# AltiumStm32Schematic.net
KiCad netlist of a schematic drawn in Altium Designer
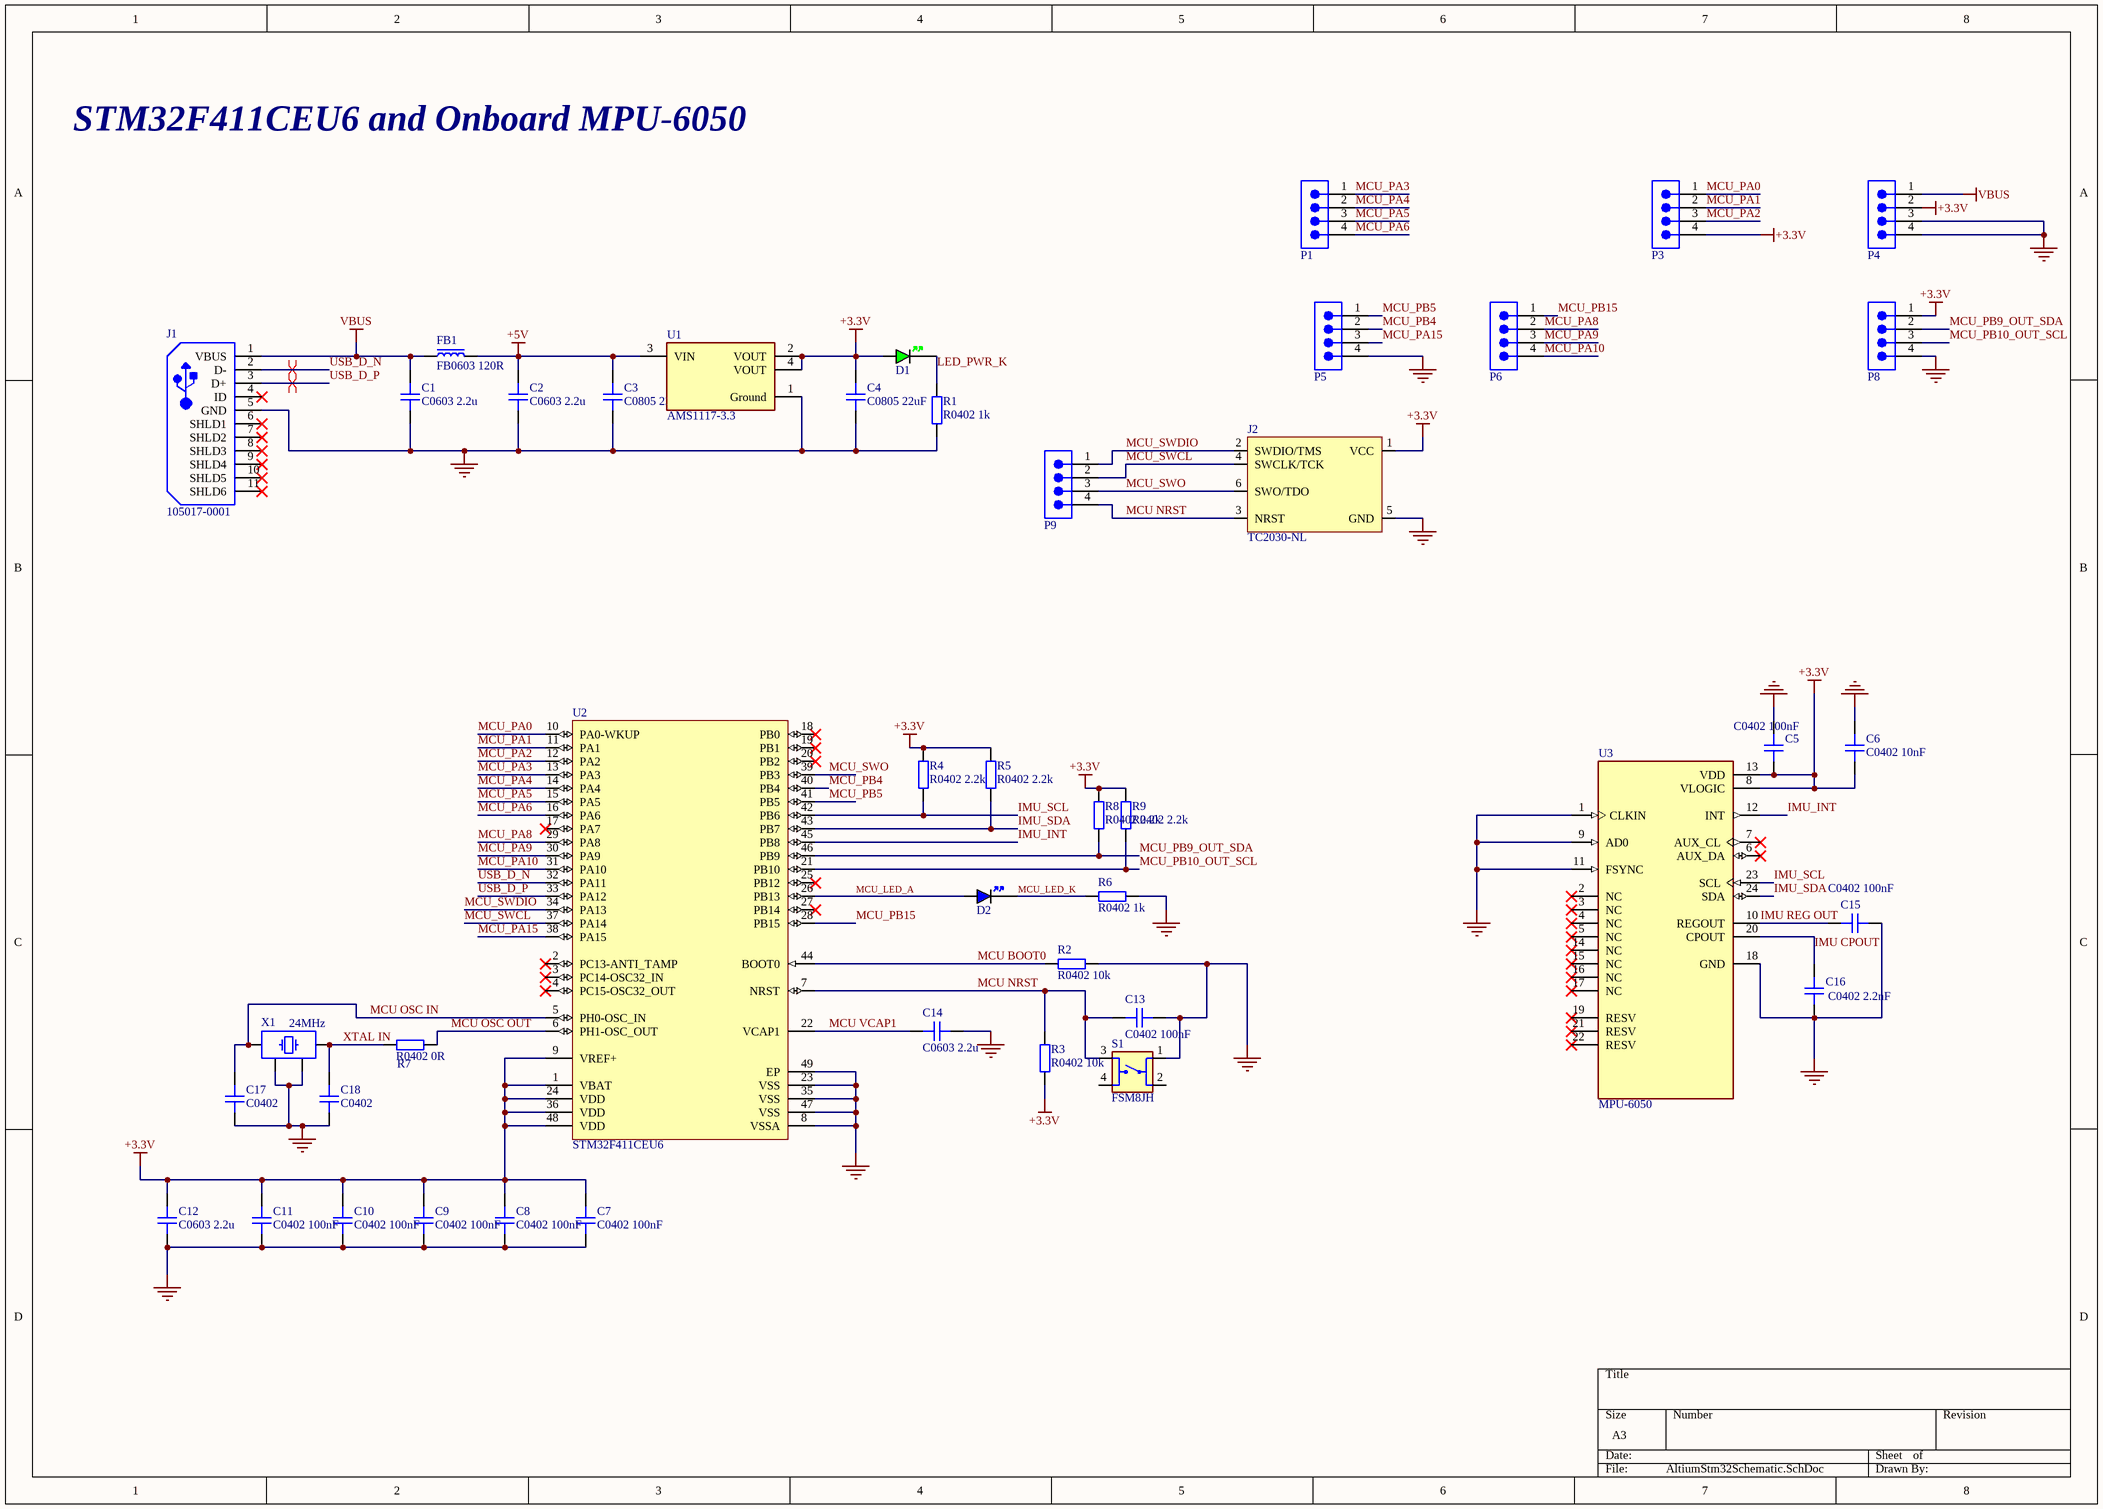
[diagram p0: AltiumStm32Schematic.SchDoc]

(export (version "E")
  (design (tool "Eeschema 10.0.6"))
  (components
    (comp (ref "C1")
      (value "C0603 2.2u")
      (footprint "CAP_0603")
      (description "Capacitor SMD 0603")
      (libsource (lib "Schematic-Lib-PhilsLab") (part "CAP_0603"))
    )
    (comp (ref "C2")
      (value "C0603 2.2u")
      (footprint "CAP_0603")
      (description "Capacitor SMD 0603")
      (libsource (lib "Schematic-Lib-PhilsLab") (part "CAP_0603"))
    )
    (comp (ref "C3")
      (value "C0805 22uF")
      (footprint "CAP_0805")
      (description "Capacitor SMD 0805 16V")
      (libsource (lib "Schematic-Lib-PhilsLab") (part "CAP_0805"))
    )
    (comp (ref "C4")
      (value "C0805 22uF")
      (footprint "CAP_0805")
      (description "Capacitor SMD 0805 16V")
      (libsource (lib "Schematic-Lib-PhilsLab") (part "CAP_0805"))
    )
    (comp (ref "C5")
      (value "C0402 100nF")
      (footprint "CAP_0402")
      (description "Capacitor SMD 0402")
      (libsource (lib "Schematic-Lib-PhilsLab") (part "CAP_0402"))
    )
    (comp (ref "C6")
      (value "C0402 10nF")
      (footprint "CAP_0402")
      (description "Capacitor SMD 0402")
      (libsource (lib "Schematic-Lib-PhilsLab") (part "CAP_0402"))
    )
    (comp (ref "C7")
      (value "C0402 100nF")
      (footprint "CAP_0402")
      (description "Capacitor SMD 0402")
      (libsource (lib "Schematic-Lib-PhilsLab") (part "CAP_0402"))
    )
    (comp (ref "C8")
      (value "C0402 100nF")
      (footprint "CAP_0402")
      (description "Capacitor SMD 0402")
      (libsource (lib "Schematic-Lib-PhilsLab") (part "CAP_0402"))
    )
    (comp (ref "C9")
      (value "C0402 100nF")
      (footprint "CAP_0402")
      (description "Capacitor SMD 0402")
      (libsource (lib "Schematic-Lib-PhilsLab") (part "CAP_0402"))
    )
    (comp (ref "C10")
      (value "C0402 100nF")
      (footprint "CAP_0402")
      (description "Capacitor SMD 0402")
      (libsource (lib "Schematic-Lib-PhilsLab") (part "CAP_0402"))
    )
    (comp (ref "C11")
      (value "C0402 100nF")
      (footprint "CAP_0402")
      (description "Capacitor SMD 0402")
      (libsource (lib "Schematic-Lib-PhilsLab") (part "CAP_0402"))
    )
    (comp (ref "C12")
      (value "C0603 2.2u")
      (footprint "CAP_0603")
      (description "Capacitor SMD 0603")
      (libsource (lib "Schematic-Lib-PhilsLab") (part "CAP_0603"))
    )
    (comp (ref "C13")
      (value "C0402 100nF")
      (footprint "CAP_0402")
      (description "Capacitor SMD 0402")
      (libsource (lib "Schematic-Lib-PhilsLab") (part "CAP_0402"))
    )
    (comp (ref "C14")
      (value "C0603 2.2u")
      (footprint "CAP_0603")
      (description "Capacitor SMD 0603")
      (libsource (lib "Schematic-Lib-PhilsLab") (part "CAP_0603"))
    )
    (comp (ref "C15")
      (value "C0402 100nF")
      (footprint "CAP_0402")
      (description "Capacitor SMD 0402")
      (libsource (lib "Schematic-Lib-PhilsLab") (part "CAP_0402"))
    )
    (comp (ref "C16")
      (value "C0402 2.2nF")
      (footprint "CAP_0402")
      (description "Capacitor SMD 0402")
      (libsource (lib "Schematic-Lib-PhilsLab") (part "CAP_0402"))
    )
    (comp (ref "C17")
      (value "C0402")
      (footprint "CAP_0402")
      (description "Capacitor SMD 0402 \r\nudemy'e göre 10pf")
      (libsource (lib "Schematic-Lib-PhilsLab") (part "CAP_0402"))
    )
    (comp (ref "C18")
      (value "C0402")
      (footprint "CAP_0402")
      (description "Capacitor SMD 0402 \r\nudemy'e göre 10pf")
      (libsource (lib "Schematic-Lib-PhilsLab") (part "CAP_0402"))
    )
    (comp (ref "D1")
      (value "GREEN")
      (footprint "LED_0402_GREEN")
      (description "LED 0402 GREEN SMD")
      (libsource (lib "Schematic-Lib-PhilsLab") (part "LED_0402_GREEN"))
    )
    (comp (ref "D2")
      (value "BLUE")
      (footprint "LED_0402_BLUE")
      (description "LED 0402 BLUE SMD")
      (libsource (lib "Schematic-Lib-PhilsLab") (part "LED_0402_BLUE"))
    )
    (comp (ref "FB1")
      (value "FB0603 120R")
      (footprint "FB_0603")
      (description "Ferrite Bead SMD 0603")
      (libsource (lib "Schematic-Lib-PhilsLab") (part "FB_0603"))
    )
    (comp (ref "J1")
      (value "105017-0001")
      (footprint "USB-MICRO-B_V")
      (fields (field (name "MANUFACTURER") "Molex"))
      (libsource (lib "Altium Content Vault") (part "USB-5-6SHLD"))
    )
    (comp (ref "J2")
      (value "TC2030-NL")
      (footprint "TC2030-NL-FP")
      (description "Tag-Connect No-Solder SWD Debug Connector (No Legs) DO NOT PLACE")
      (fields
        (field (name "MANUFACTURER") "Tag-Connect")
        (field (name "MANUFACTURER PART NUMBER") "TC2030-NL-FP")
      )
      (libsource (lib "Schematic-Lib-PhilsLab") (part "TC2030-NL"))
    )
    (comp (ref "P1")
      (value "61300411121")
      (footprint "61300411121")
      (description "WR-PHD Pin Header, THT, Vertical, pitch 2.54mm, 1 Row, 4P")
      (fields (field (name "MANUFACTURER") "Wurth Elektronik"))
      (libsource (lib "Altium_WR-PHD (rev24a)") (part "61300411121"))
    )
    (comp (ref "P3")
      (value "61300411121")
      (footprint "61300411121")
      (description "WR-PHD Pin Header, THT, Vertical, pitch 2.54mm, 1 Row, 4P")
      (fields (field (name "MANUFACTURER") "Wurth Elektronik"))
      (libsource (lib "Altium_WR-PHD (rev24a)") (part "61300411121"))
    )
    (comp (ref "P4")
      (value "61300411121")
      (footprint "61300411121")
      (description "WR-PHD Pin Header, THT, Vertical, pitch 2.54mm, 1 Row, 4P")
      (fields (field (name "MANUFACTURER") "Wurth Elektronik"))
      (libsource (lib "Altium_WR-PHD (rev24a)") (part "61300411121"))
    )
    (comp (ref "P5")
      (value "61300411121")
      (footprint "61300411121")
      (description "WR-PHD Pin Header, THT, Vertical, pitch 2.54mm, 1 Row, 4P")
      (fields (field (name "MANUFACTURER") "Wurth Elektronik"))
      (libsource (lib "Altium_WR-PHD (rev24a)") (part "61300411121"))
    )
    (comp (ref "P6")
      (value "61300411121")
      (footprint "61300411121")
      (description "WR-PHD Pin Header, THT, Vertical, pitch 2.54mm, 1 Row, 4P")
      (fields (field (name "MANUFACTURER") "Wurth Elektronik"))
      (libsource (lib "Altium_WR-PHD (rev24a)") (part "61300411121"))
    )
    (comp (ref "P8")
      (value "61300411121")
      (footprint "61300411121")
      (description "WR-PHD Pin Header, THT, Vertical, pitch 2.54mm, 1 Row, 4P")
      (fields (field (name "MANUFACTURER") "Wurth Elektronik"))
      (libsource (lib "Altium_WR-PHD (rev24a)") (part "61300411121"))
    )
    (comp (ref "P9")
      (value "61300411121")
      (footprint "61300411121")
      (description "WR-PHD Pin Header, THT, Vertical, pitch 2.54mm, 1 Row, 4P")
      (fields (field (name "MANUFACTURER") "Wurth Elektronik"))
      (libsource (lib "Altium_WR-PHD (rev24a)") (part "61300411121"))
    )
    (comp (ref "R1")
      (value "R0402 1k")
      (footprint "RES_0402")
      (description "Resistor SMD 0402")
      (libsource (lib "Schematic-Lib-PhilsLab") (part "RES_0402"))
    )
    (comp (ref "R2")
      (value "R0402 10k")
      (footprint "RES_0402")
      (description "Resistor SMD 0402")
      (libsource (lib "Schematic-Lib-PhilsLab") (part "RES_0402"))
    )
    (comp (ref "R3")
      (value "R0402 10k")
      (footprint "RES_0402")
      (description "Resistor SMD 0402")
      (libsource (lib "Schematic-Lib-PhilsLab") (part "RES_0402"))
    )
    (comp (ref "R4")
      (value "R0402 2.2k")
      (footprint "RES_0402")
      (description "Resistor SMD 0402")
      (libsource (lib "Schematic-Lib-PhilsLab") (part "RES_0402"))
    )
    (comp (ref "R5")
      (value "R0402 2.2k")
      (footprint "RES_0402")
      (description "Resistor SMD 0402")
      (libsource (lib "Schematic-Lib-PhilsLab") (part "RES_0402"))
    )
    (comp (ref "R6")
      (value "R0402 1k")
      (footprint "RES_0402")
      (description "Resistor SMD 0402")
      (libsource (lib "Schematic-Lib-PhilsLab") (part "RES_0402"))
    )
    (comp (ref "R7")
      (value "R0402 0R")
      (footprint "RES_0402")
      (description "Resistor SMD 0402")
      (libsource (lib "Schematic-Lib-PhilsLab") (part "RES_0402"))
    )
    (comp (ref "R8")
      (value "R0402 2.2k")
      (footprint "RES_0402")
      (description "Resistor SMD 0402")
      (libsource (lib "Schematic-Lib-PhilsLab") (part "RES_0402"))
    )
    (comp (ref "R9")
      (value "R0402 2.2k")
      (footprint "RES_0402")
      (description "Resistor SMD 0402")
      (libsource (lib "Schematic-Lib-PhilsLab") (part "RES_0402"))
    )
    (comp (ref "S1")
      (value "FSM8JH")
      (footprint "SW_FSM8JH")
      (description "Tactile Switch SPST-NO Top Actuated Through Hole")
      (fields (field (name "MF") "TE Connectivity"))
      (libsource (lib "FSM8JH") (part "FSM8JH"))
    )
    (comp (ref "U1")
      (value "AMS1117-3.3")
      (footprint "FP-AMS1117-IPC_C")
      (description "LDO Voltage Regulators 1A, 3.3V")
      (fields
        (field (name "OCTOPART") "https://octopart.com/ams1117-3.3-advanced+monolithic+systems-25899300")
        (field (name "MANUFACTURER") "Advanced Monolithic Systems")
      )
      (libsource (lib "Altium Content Vault") (part "8bdbb5f8e77002000e30dd2845d0354"))
    )
    (comp (ref "U2")
      (value "STM32F411CEU6")
      (footprint "STM-UFQFPN48_L")
      (libsource (lib "Altium Content Vault") (part "MC-ARM-STM32F411-UFQFPN48"))
    )
    (comp (ref "U3")
      (value "MPU-6050")
      (footprint "QFN50P400X400X95-24N")
      (description "MPU-6050 series Accelerometer, Gyroscope, 3 Axis Sensor Evaluation Board")
      (fields (field (name "MF") "TDK InvenSense"))
      (libsource (lib "MPU-6050") (part "MPU-6050"))
    )
    (comp (ref "X1")
      (value "24MHz")
      (footprint "XTAL_3225")
      (description "Crystal SMD 24MHz 10PPM 7pF 3225")
      (fields
        (field (name "MANUFACTURER") "Epson")
        (field (name "MANUFACTURER PART NUMBER") "TSX-3225 24.0000MF15X-AC")
      )
      (libsource (lib "Schematic-Lib-PhilsLab") (part "TSX-3225_24.0000MF15X-AC"))
    )
  )
  (nets
    (net (code "1") (name "+3.3V") (class "Default")
      (node (ref "C10") (pin "1") (pinfunction "1_1") (pintype "passive"))
      (node (ref "C11") (pin "1") (pinfunction "1_1") (pintype "passive"))
      (node (ref "C12") (pin "2") (pinfunction "2_2") (pintype "passive"))
      (node (ref "C4") (pin "2") (pinfunction "2_2") (pintype "passive"))
      (node (ref "C5") (pin "1") (pinfunction "1_1") (pintype "passive"))
      (node (ref "C6") (pin "1") (pinfunction "1_1") (pintype "passive"))
      (node (ref "C7") (pin "1") (pinfunction "1_1") (pintype "passive"))
      (node (ref "C8") (pin "1") (pinfunction "1_1") (pintype "passive"))
      (node (ref "C9") (pin "1") (pinfunction "1_1") (pintype "passive"))
      (node (ref "D1") (pin "A") (pinfunction "A_A") (pintype "passive"))
      (node (ref "J2") (pin "1") (pinfunction "VCC_1") (pintype "passive"))
      (node (ref "P3") (pin "4") (pinfunction "4_4") (pintype "passive"))
      (node (ref "P4") (pin "2") (pinfunction "2_2") (pintype "passive"))
      (node (ref "P8") (pin "1") (pinfunction "1_1") (pintype "passive"))
      (node (ref "R3") (pin "2") (pinfunction "2_2") (pintype "passive"))
      (node (ref "R4") (pin "2") (pinfunction "2_2") (pintype "passive"))
      (node (ref "R5") (pin "2") (pinfunction "2_2") (pintype "passive"))
      (node (ref "R8") (pin "2") (pinfunction "2_2") (pintype "passive"))
      (node (ref "R9") (pin "2") (pinfunction "2_2") (pintype "passive"))
      (node (ref "U1") (pin "2") (pinfunction "VOUT_2") (pintype "passive"))
      (node (ref "U1") (pin "4") (pinfunction "VOUT_4") (pintype "passive"))
      (node (ref "U2") (pin "1") (pinfunction "VBAT_1") (pintype "power_in"))
      (node (ref "U2") (pin "24") (pinfunction "VDD_24") (pintype "power_in"))
      (node (ref "U2") (pin "36") (pinfunction "VDD_36") (pintype "power_in"))
      (node (ref "U2") (pin "48") (pinfunction "VDD_48") (pintype "power_in"))
      (node (ref "U2") (pin "9") (pinfunction "VREF+_9") (pintype "power_in"))
      (node (ref "U3") (pin "13") (pinfunction "VDD_13") (pintype "power_in"))
      (node (ref "U3") (pin "8") (pinfunction "VLOGIC_8") (pintype "power_in"))
    )
    (net (code "2") (name "+5V") (class "Default")
      (node (ref "C2") (pin "2") (pinfunction "2_2") (pintype "passive"))
      (node (ref "C3") (pin "2") (pinfunction "2_2") (pintype "passive"))
      (node (ref "FB1") (pin "2") (pinfunction "2_2") (pintype "passive"))
      (node (ref "U1") (pin "3") (pinfunction "VIN_3") (pintype "power_in"))
    )
    (net (code "3") (name "/IMU CPOUT") (class "Default")
      (node (ref "C16") (pin "2") (pinfunction "2_2") (pintype "passive"))
      (node (ref "U3") (pin "20") (pinfunction "CPOUT_20") (pintype "passive"))
    )
    (net (code "4") (name "/IMU REG OUT") (class "Default")
      (node (ref "C15") (pin "1") (pinfunction "1_1") (pintype "passive"))
      (node (ref "U3") (pin "10") (pinfunction "REGOUT_10") (pintype "passive"))
    )
    (net (code "5") (name "/IMU_INT") (class "Default")
      (node (ref "U2") (pin "45") (pinfunction "PB8_45") (pintype "bidirectional"))
      (node (ref "U3") (pin "12") (pinfunction "INT_12") (pintype "output"))
    )
    (net (code "6") (name "/IMU_SCL") (class "Default")
      (node (ref "R4") (pin "1") (pinfunction "1_1") (pintype "passive"))
      (node (ref "U2") (pin "42") (pinfunction "PB6_42") (pintype "bidirectional"))
      (node (ref "U3") (pin "23") (pinfunction "SCL_23") (pintype "input"))
    )
    (net (code "7") (name "/IMU_SDA") (class "Default")
      (node (ref "R5") (pin "1") (pinfunction "1_1") (pintype "passive"))
      (node (ref "U2") (pin "43") (pinfunction "PB7_43") (pintype "bidirectional"))
      (node (ref "U3") (pin "24") (pinfunction "SDA_24") (pintype "bidirectional"))
    )
    (net (code "8") (name "/LED_PWR_K") (class "Default")
      (node (ref "D1") (pin "K") (pinfunction "K_K") (pintype "passive"))
      (node (ref "R1") (pin "2") (pinfunction "2_2") (pintype "passive"))
    )
    (net (code "9") (name "/MCU BOOT0") (class "Default")
      (node (ref "R2") (pin "2") (pinfunction "2_2") (pintype "passive"))
      (node (ref "U2") (pin "44") (pinfunction "BOOT0_44") (pintype "input"))
    )
    (net (code "10") (name "/MCU NRST") (class "Default")
      (node (ref "C13") (pin "2") (pinfunction "2_2") (pintype "passive"))
      (node (ref "J2") (pin "3") (pinfunction "NRST_3") (pintype "passive"))
      (node (ref "P9") (pin "4") (pinfunction "4_4") (pintype "passive"))
      (node (ref "R3") (pin "1") (pinfunction "1_1") (pintype "passive"))
      (node (ref "S1") (pin "3") (pinfunction "3_3") (pintype "passive"))
      (node (ref "U2") (pin "7") (pinfunction "NRST_7") (pintype "bidirectional"))
    )
    (net (code "11") (name "/MCU OSC IN") (class "Default")
      (node (ref "C17") (pin "2") (pinfunction "2_2") (pintype "passive"))
      (node (ref "U2") (pin "5") (pinfunction "PH0-OSC_IN_5") (pintype "bidirectional"))
      (node (ref "X1") (pin "1") (pinfunction "1_1") (pintype "passive"))
    )
    (net (code "12") (name "/MCU OSC OUT") (class "Default")
      (node (ref "R7") (pin "2") (pinfunction "2_2") (pintype "passive"))
      (node (ref "U2") (pin "6") (pinfunction "PH1-OSC_OUT_6") (pintype "bidirectional"))
    )
    (net (code "13") (name "/MCU VCAP1") (class "Default")
      (node (ref "C14") (pin "2") (pinfunction "2_2") (pintype "passive"))
      (node (ref "U2") (pin "22") (pinfunction "VCAP1_22") (pintype "passive"))
    )
    (net (code "14") (name "/MCU_LED_A") (class "Default")
      (node (ref "D2") (pin "A") (pinfunction "A_A") (pintype "passive"))
      (node (ref "U2") (pin "26") (pinfunction "PB13_26") (pintype "bidirectional"))
    )
    (net (code "15") (name "/MCU_LED_K") (class "Default")
      (node (ref "D2") (pin "K") (pinfunction "K_K") (pintype "passive"))
      (node (ref "R6") (pin "2") (pinfunction "2_2") (pintype "passive"))
    )
    (net (code "16") (name "/MCU_PA0") (class "Default")
      (node (ref "P3") (pin "1") (pinfunction "1_1") (pintype "passive"))
      (node (ref "U2") (pin "10") (pinfunction "PA0-WKUP_10") (pintype "bidirectional"))
    )
    (net (code "17") (name "/MCU_PA1") (class "Default")
      (node (ref "P3") (pin "2") (pinfunction "2_2") (pintype "passive"))
      (node (ref "U2") (pin "11") (pinfunction "PA1_11") (pintype "bidirectional"))
    )
    (net (code "18") (name "/MCU_PA2") (class "Default")
      (node (ref "P3") (pin "3") (pinfunction "3_3") (pintype "passive"))
      (node (ref "U2") (pin "12") (pinfunction "PA2_12") (pintype "bidirectional"))
    )
    (net (code "19") (name "/MCU_PA3") (class "Default")
      (node (ref "P1") (pin "1") (pinfunction "1_1") (pintype "passive"))
      (node (ref "U2") (pin "13") (pinfunction "PA3_13") (pintype "bidirectional"))
    )
    (net (code "20") (name "/MCU_PA4") (class "Default")
      (node (ref "P1") (pin "2") (pinfunction "2_2") (pintype "passive"))
      (node (ref "U2") (pin "14") (pinfunction "PA4_14") (pintype "bidirectional"))
    )
    (net (code "21") (name "/MCU_PA5") (class "Default")
      (node (ref "P1") (pin "3") (pinfunction "3_3") (pintype "passive"))
      (node (ref "U2") (pin "15") (pinfunction "PA5_15") (pintype "bidirectional"))
    )
    (net (code "22") (name "/MCU_PA6") (class "Default")
      (node (ref "P1") (pin "4") (pinfunction "4_4") (pintype "passive"))
      (node (ref "U2") (pin "16") (pinfunction "PA6_16") (pintype "bidirectional"))
    )
    (net (code "23") (name "/MCU_PA8") (class "Default")
      (node (ref "P6") (pin "2") (pinfunction "2_2") (pintype "passive"))
      (node (ref "U2") (pin "29") (pinfunction "PA8_29") (pintype "bidirectional"))
    )
    (net (code "24") (name "/MCU_PA9") (class "Default")
      (node (ref "P6") (pin "3") (pinfunction "3_3") (pintype "passive"))
      (node (ref "U2") (pin "30") (pinfunction "PA9_30") (pintype "bidirectional"))
    )
    (net (code "25") (name "/MCU_PA10") (class "Default")
      (node (ref "P6") (pin "4") (pinfunction "4_4") (pintype "passive"))
      (node (ref "U2") (pin "31") (pinfunction "PA10_31") (pintype "bidirectional"))
    )
    (net (code "26") (name "/MCU_PA15") (class "Default")
      (node (ref "P5") (pin "3") (pinfunction "3_3") (pintype "passive"))
      (node (ref "U2") (pin "38") (pinfunction "PA15_38") (pintype "bidirectional"))
    )
    (net (code "27") (name "/MCU_PB4") (class "Default")
      (node (ref "P5") (pin "2") (pinfunction "2_2") (pintype "passive"))
      (node (ref "U2") (pin "40") (pinfunction "PB4_40") (pintype "bidirectional"))
    )
    (net (code "28") (name "/MCU_PB5") (class "Default")
      (node (ref "P5") (pin "1") (pinfunction "1_1") (pintype "passive"))
      (node (ref "U2") (pin "41") (pinfunction "PB5_41") (pintype "bidirectional"))
    )
    (net (code "29") (name "/MCU_PB9_OUT_SDA") (class "Default")
      (node (ref "P8") (pin "2") (pinfunction "2_2") (pintype "passive"))
      (node (ref "R8") (pin "1") (pinfunction "1_1") (pintype "passive"))
      (node (ref "U2") (pin "46") (pinfunction "PB9_46") (pintype "bidirectional"))
    )
    (net (code "30") (name "/MCU_PB10_OUT_SCL") (class "Default")
      (node (ref "P8") (pin "3") (pinfunction "3_3") (pintype "passive"))
      (node (ref "R9") (pin "1") (pinfunction "1_1") (pintype "passive"))
      (node (ref "U2") (pin "21") (pinfunction "PB10_21") (pintype "bidirectional"))
    )
    (net (code "31") (name "/MCU_PB15") (class "Default")
      (node (ref "P6") (pin "1") (pinfunction "1_1") (pintype "passive"))
      (node (ref "U2") (pin "28") (pinfunction "PB15_28") (pintype "bidirectional"))
    )
    (net (code "32") (name "/MCU_SWCL") (class "Default")
      (node (ref "J2") (pin "4") (pinfunction "SWCLK/TCK_4") (pintype "passive"))
      (node (ref "P9") (pin "2") (pinfunction "2_2") (pintype "passive"))
      (node (ref "U2") (pin "37") (pinfunction "PA14_37") (pintype "bidirectional"))
    )
    (net (code "33") (name "/MCU_SWDIO") (class "Default")
      (node (ref "J2") (pin "2") (pinfunction "SWDIO/TMS_2") (pintype "passive"))
      (node (ref "P9") (pin "1") (pinfunction "1_1") (pintype "passive"))
      (node (ref "U2") (pin "34") (pinfunction "PA13_34") (pintype "bidirectional"))
    )
    (net (code "34") (name "/MCU_SWO") (class "Default")
      (node (ref "J2") (pin "6") (pinfunction "SWO/TDO_6") (pintype "passive"))
      (node (ref "P9") (pin "3") (pinfunction "3_3") (pintype "passive"))
      (node (ref "U2") (pin "39") (pinfunction "PB3_39") (pintype "bidirectional"))
    )
    (net (code "35") (name "/USB_D_N") (class "Default")
      (node (ref "J1") (pin "2") (pinfunction "D-_2") (pintype "passive"))
      (node (ref "U2") (pin "32") (pinfunction "PA11_32") (pintype "bidirectional"))
    )
    (net (code "36") (name "/USB_D_P") (class "Default")
      (node (ref "J1") (pin "3") (pinfunction "D+_3") (pintype "passive"))
      (node (ref "U2") (pin "33") (pinfunction "PA12_33") (pintype "bidirectional"))
    )
    (net (code "37") (name "/XTAL IN") (class "Default")
      (node (ref "C18") (pin "2") (pinfunction "2_2") (pintype "passive"))
      (node (ref "R7") (pin "1") (pinfunction "1_1") (pintype "passive"))
      (node (ref "X1") (pin "3") (pinfunction "3_3") (pintype "passive"))
    )
    (net (code "38") (name "GND") (class "Default")
      (node (ref "C1") (pin "1") (pinfunction "1_1") (pintype "passive"))
      (node (ref "C10") (pin "2") (pinfunction "2_2") (pintype "passive"))
      (node (ref "C11") (pin "2") (pinfunction "2_2") (pintype "passive"))
      (node (ref "C12") (pin "1") (pinfunction "1_1") (pintype "passive"))
      (node (ref "C13") (pin "1") (pinfunction "1_1") (pintype "passive"))
      (node (ref "C14") (pin "1") (pinfunction "1_1") (pintype "passive"))
      (node (ref "C15") (pin "2") (pinfunction "2_2") (pintype "passive"))
      (node (ref "C16") (pin "1") (pinfunction "1_1") (pintype "passive"))
      (node (ref "C17") (pin "1") (pinfunction "1_1") (pintype "passive"))
      (node (ref "C18") (pin "1") (pinfunction "1_1") (pintype "passive"))
      (node (ref "C2") (pin "1") (pinfunction "1_1") (pintype "passive"))
      (node (ref "C3") (pin "1") (pinfunction "1_1") (pintype "passive"))
      (node (ref "C4") (pin "1") (pinfunction "1_1") (pintype "passive"))
      (node (ref "C5") (pin "2") (pinfunction "2_2") (pintype "passive"))
      (node (ref "C6") (pin "2") (pinfunction "2_2") (pintype "passive"))
      (node (ref "C7") (pin "2") (pinfunction "2_2") (pintype "passive"))
      (node (ref "C8") (pin "2") (pinfunction "2_2") (pintype "passive"))
      (node (ref "C9") (pin "2") (pinfunction "2_2") (pintype "passive"))
      (node (ref "J1") (pin "5") (pinfunction "GND_5") (pintype "passive"))
      (node (ref "J2") (pin "5") (pinfunction "GND_5") (pintype "passive"))
      (node (ref "P4") (pin "3") (pinfunction "3_3") (pintype "passive"))
      (node (ref "P4") (pin "4") (pinfunction "4_4") (pintype "passive"))
      (node (ref "P5") (pin "4") (pinfunction "4_4") (pintype "passive"))
      (node (ref "P8") (pin "4") (pinfunction "4_4") (pintype "passive"))
      (node (ref "R1") (pin "1") (pinfunction "1_1") (pintype "passive"))
      (node (ref "R2") (pin "1") (pinfunction "1_1") (pintype "passive"))
      (node (ref "R6") (pin "1") (pinfunction "1_1") (pintype "passive"))
      (node (ref "S1") (pin "1") (pinfunction "1_1") (pintype "passive"))
      (node (ref "U1") (pin "1") (pinfunction "Ground_1") (pintype "power_in"))
      (node (ref "U2") (pin "23") (pinfunction "VSS_23") (pintype "power_in"))
      (node (ref "U2") (pin "35") (pinfunction "VSS_35") (pintype "power_in"))
      (node (ref "U2") (pin "47") (pinfunction "VSS_47") (pintype "power_in"))
      (node (ref "U2") (pin "49") (pinfunction "EP_49") (pintype "power_in"))
      (node (ref "U2") (pin "8") (pinfunction "VSSA_8") (pintype "power_in"))
      (node (ref "U3") (pin "1") (pinfunction "CLKIN_1") (pintype "input"))
      (node (ref "U3") (pin "11") (pinfunction "FSYNC_11") (pintype "input"))
      (node (ref "U3") (pin "18") (pinfunction "GND_18") (pintype "power_in"))
      (node (ref "U3") (pin "9") (pinfunction "AD0_9") (pintype "input"))
      (node (ref "X1") (pin "2") (pinfunction "2_2") (pintype "passive"))
      (node (ref "X1") (pin "4") (pinfunction "4_4") (pintype "passive"))
    )
    (net (code "39") (name "VBUS") (class "Default")
      (node (ref "C1") (pin "2") (pinfunction "2_2") (pintype "passive"))
      (node (ref "FB1") (pin "1") (pinfunction "1_1") (pintype "passive"))
      (node (ref "J1") (pin "1") (pinfunction "VBUS_1") (pintype "passive"))
      (node (ref "P4") (pin "1") (pinfunction "1_1") (pintype "passive"))
    )
    (net (code "40") (name "unconnected-(J1-ID-Pad4)") (class "Default")
      (node (ref "J1") (pin "4") (pinfunction "ID_4") (pintype "passive+no_connect"))
    )
    (net (code "41") (name "unconnected-(J1-SHLD1-Pad6)") (class "Default")
      (node (ref "J1") (pin "6") (pinfunction "SHLD1_6") (pintype "passive+no_connect"))
    )
    (net (code "42") (name "unconnected-(J1-SHLD2-Pad7)") (class "Default")
      (node (ref "J1") (pin "7") (pinfunction "SHLD2_7") (pintype "passive+no_connect"))
    )
    (net (code "43") (name "unconnected-(J1-SHLD3-Pad8)") (class "Default")
      (node (ref "J1") (pin "8") (pinfunction "SHLD3_8") (pintype "passive+no_connect"))
    )
    (net (code "44") (name "unconnected-(J1-SHLD4-Pad9)") (class "Default")
      (node (ref "J1") (pin "9") (pinfunction "SHLD4_9") (pintype "passive+no_connect"))
    )
    (net (code "45") (name "unconnected-(J1-SHLD5-Pad10)") (class "Default")
      (node (ref "J1") (pin "10") (pinfunction "SHLD5_10") (pintype "passive+no_connect"))
    )
    (net (code "46") (name "unconnected-(J1-SHLD6-Pad11)") (class "Default")
      (node (ref "J1") (pin "11") (pinfunction "SHLD6_11") (pintype "passive+no_connect"))
    )
    (net (code "47") (name "unconnected-(S1-Pad2)") (class "Default")
      (node (ref "S1") (pin "2") (pinfunction "2_2") (pintype "passive"))
    )
    (net (code "48") (name "unconnected-(S1-Pad4)") (class "Default")
      (node (ref "S1") (pin "4") (pinfunction "4_4") (pintype "passive"))
    )
    (net (code "49") (name "unconnected-(U2-PA7-Pad17)") (class "Default")
      (node (ref "U2") (pin "17") (pinfunction "PA7_17") (pintype "bidirectional+no_connect"))
    )
    (net (code "50") (name "unconnected-(U2-PB0-Pad18)") (class "Default")
      (node (ref "U2") (pin "18") (pinfunction "PB0_18") (pintype "bidirectional+no_connect"))
    )
    (net (code "51") (name "unconnected-(U2-PB1-Pad19)") (class "Default")
      (node (ref "U2") (pin "19") (pinfunction "PB1_19") (pintype "bidirectional+no_connect"))
    )
    (net (code "52") (name "unconnected-(U2-PB2-Pad20)") (class "Default")
      (node (ref "U2") (pin "20") (pinfunction "PB2_20") (pintype "bidirectional+no_connect"))
    )
    (net (code "53") (name "unconnected-(U2-PB12-Pad25)") (class "Default")
      (node (ref "U2") (pin "25") (pinfunction "PB12_25") (pintype "bidirectional+no_connect"))
    )
    (net (code "54") (name "unconnected-(U2-PB14-Pad27)") (class "Default")
      (node (ref "U2") (pin "27") (pinfunction "PB14_27") (pintype "bidirectional+no_connect"))
    )
    (net (code "55") (name "unconnected-(U2-PC13-ANTI_TAMP-Pad2)") (class "Default")
      (node (ref "U2") (pin "2") (pinfunction "PC13-ANTI_TAMP_2") (pintype "bidirectional+no_connect"))
    )
    (net (code "56") (name "unconnected-(U2-PC14-OSC32_IN-Pad3)") (class "Default")
      (node (ref "U2") (pin "3") (pinfunction "PC14-OSC32_IN_3") (pintype "bidirectional+no_connect"))
    )
    (net (code "57") (name "unconnected-(U2-PC15-OSC32_OUT-Pad4)") (class "Default")
      (node (ref "U2") (pin "4") (pinfunction "PC15-OSC32_OUT_4") (pintype "bidirectional+no_connect"))
    )
    (net (code "58") (name "unconnected-(U3-AUX_CL-Pad7)") (class "Default")
      (node (ref "U3") (pin "7") (pinfunction "AUX_CL_7") (pintype "output+no_connect"))
    )
    (net (code "59") (name "unconnected-(U3-AUX_DA-Pad6)") (class "Default")
      (node (ref "U3") (pin "6") (pinfunction "AUX_DA_6") (pintype "bidirectional+no_connect"))
    )
    (net (code "60") (name "unconnected-(U3-NC-Pad2)") (class "Default")
      (node (ref "U3") (pin "2") (pinfunction "NC_2") (pintype "passive+no_connect"))
    )
    (net (code "61") (name "unconnected-(U3-NC-Pad3)") (class "Default")
      (node (ref "U3") (pin "3") (pinfunction "NC_3") (pintype "passive+no_connect"))
    )
    (net (code "62") (name "unconnected-(U3-NC-Pad4)") (class "Default")
      (node (ref "U3") (pin "4") (pinfunction "NC_4") (pintype "passive+no_connect"))
    )
    (net (code "63") (name "unconnected-(U3-NC-Pad5)") (class "Default")
      (node (ref "U3") (pin "5") (pinfunction "NC_5") (pintype "passive+no_connect"))
    )
    (net (code "64") (name "unconnected-(U3-NC-Pad14)") (class "Default")
      (node (ref "U3") (pin "14") (pinfunction "NC_14") (pintype "passive+no_connect"))
    )
    (net (code "65") (name "unconnected-(U3-NC-Pad15)") (class "Default")
      (node (ref "U3") (pin "15") (pinfunction "NC_15") (pintype "passive+no_connect"))
    )
    (net (code "66") (name "unconnected-(U3-NC-Pad16)") (class "Default")
      (node (ref "U3") (pin "16") (pinfunction "NC_16") (pintype "passive+no_connect"))
    )
    (net (code "67") (name "unconnected-(U3-NC-Pad17)") (class "Default")
      (node (ref "U3") (pin "17") (pinfunction "NC_17") (pintype "passive+no_connect"))
    )
    (net (code "68") (name "unconnected-(U3-RESV-Pad19)") (class "Default")
      (node (ref "U3") (pin "19") (pinfunction "RESV_19") (pintype "passive+no_connect"))
    )
    (net (code "69") (name "unconnected-(U3-RESV-Pad21)") (class "Default")
      (node (ref "U3") (pin "21") (pinfunction "RESV_21") (pintype "passive+no_connect"))
    )
    (net (code "70") (name "unconnected-(U3-RESV-Pad22)") (class "Default")
      (node (ref "U3") (pin "22") (pinfunction "RESV_22") (pintype "passive+no_connect"))
    )
  )
)
